# PowerSupply.net
KiCad netlist of a schematic drawn in Altium Designer
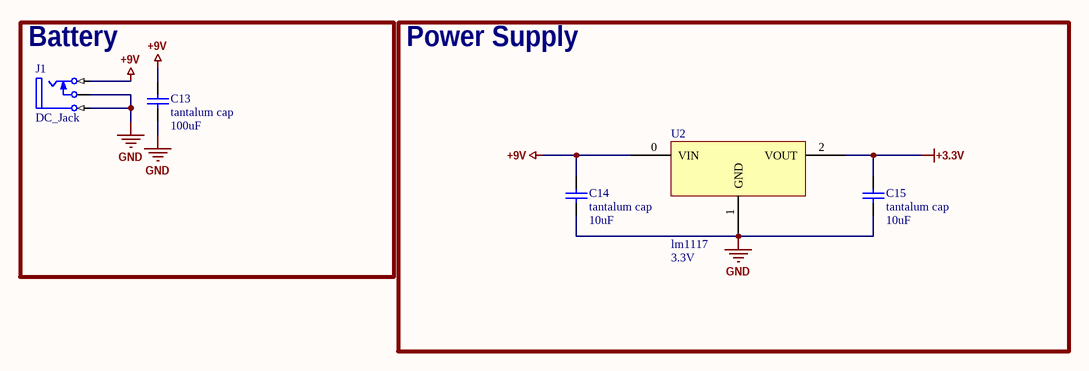
[diagram p0: PowerSupply.SchDoc]

(export (version "E")
  (design (tool "Eeschema 10.0.6"))
  (components
    (comp (ref "C13")
      (value "tantalum cap")
      (footprint "C1206tancap")
      (description "Capacitor (Semiconductor SIM Model)")
      (fields (field (name "ALTIUM_VALUE") "100uF") (field (name "PUBLISHER") "Altium Limited"))
      (libsource (lib "smartmcu") (part "Cap Semi_6"))
    )
    (comp (ref "C14")
      (value "tantalum cap")
      (footprint "C1206tancap")
      (description "Capacitor (Semiconductor SIM Model)")
      (fields (field (name "ALTIUM_VALUE") "10uF") (field (name "PUBLISHER") "Altium Limited"))
      (libsource (lib "smartmcu") (part "Cap Semi_5"))
    )
    (comp (ref "C15")
      (value "tantalum cap")
      (footprint "C1206tancap")
      (description "Capacitor (Semiconductor SIM Model)")
      (fields (field (name "ALTIUM_VALUE") "10uF") (field (name "PUBLISHER") "Altium Limited"))
      (libsource (lib "smartmcu") (part "Cap Semi_5"))
    )
    (comp (ref "J1")
      (value "DC_Jack")
      (footprint "My_DC_Jack")
      (fields (field (name "ASID PART NUMBER") "DC_Jack-AS"))
      (libsource (lib "Mylib+Rev+4") (part "DC_Jack"))
    )
    (comp (ref "U2")
      (value "lm1117")
      (footprint "4-Pin SOT")
      (fields (field (name "OUTPUT VOLTAG") "3.3V"))
      (libsource (lib "smartmcu") (part "lm1117"))
    )
  )
  (nets
    (net (code "1") (name "+3.3V") (class "Default")
      (node (ref "C15") (pin "2") (pinfunction "2_2") (pintype "passive"))
      (node (ref "U2") (pin "2") (pinfunction "VOUT_2") (pintype "passive"))
    )
    (net (code "2") (name "+9V") (class "Default")
      (node (ref "C13") (pin "2") (pinfunction "2_2") (pintype "passive"))
      (node (ref "C14") (pin "2") (pinfunction "2_2") (pintype "passive"))
      (node (ref "J1") (pin "1") (pinfunction "T_1") (pintype "input"))
      (node (ref "U2") (pin "0") (pinfunction "VIN_0") (pintype "passive"))
    )
    (net (code "3") (name "GND") (class "Default")
      (node (ref "C13") (pin "1") (pinfunction "1_1") (pintype "passive"))
      (node (ref "C14") (pin "1") (pinfunction "1_1") (pintype "passive"))
      (node (ref "C15") (pin "1") (pinfunction "1_1") (pintype "passive"))
      (node (ref "J1") (pin "2") (pinfunction "TN_2") (pintype "passive"))
      (node (ref "J1") (pin "3") (pinfunction "S_3") (pintype "input"))
      (node (ref "U2") (pin "1") (pinfunction "GND_1") (pintype "passive"))
    )
  )
)
